# 23005_1.net
KiCad netlist of a schematic drawn in Altium Designer
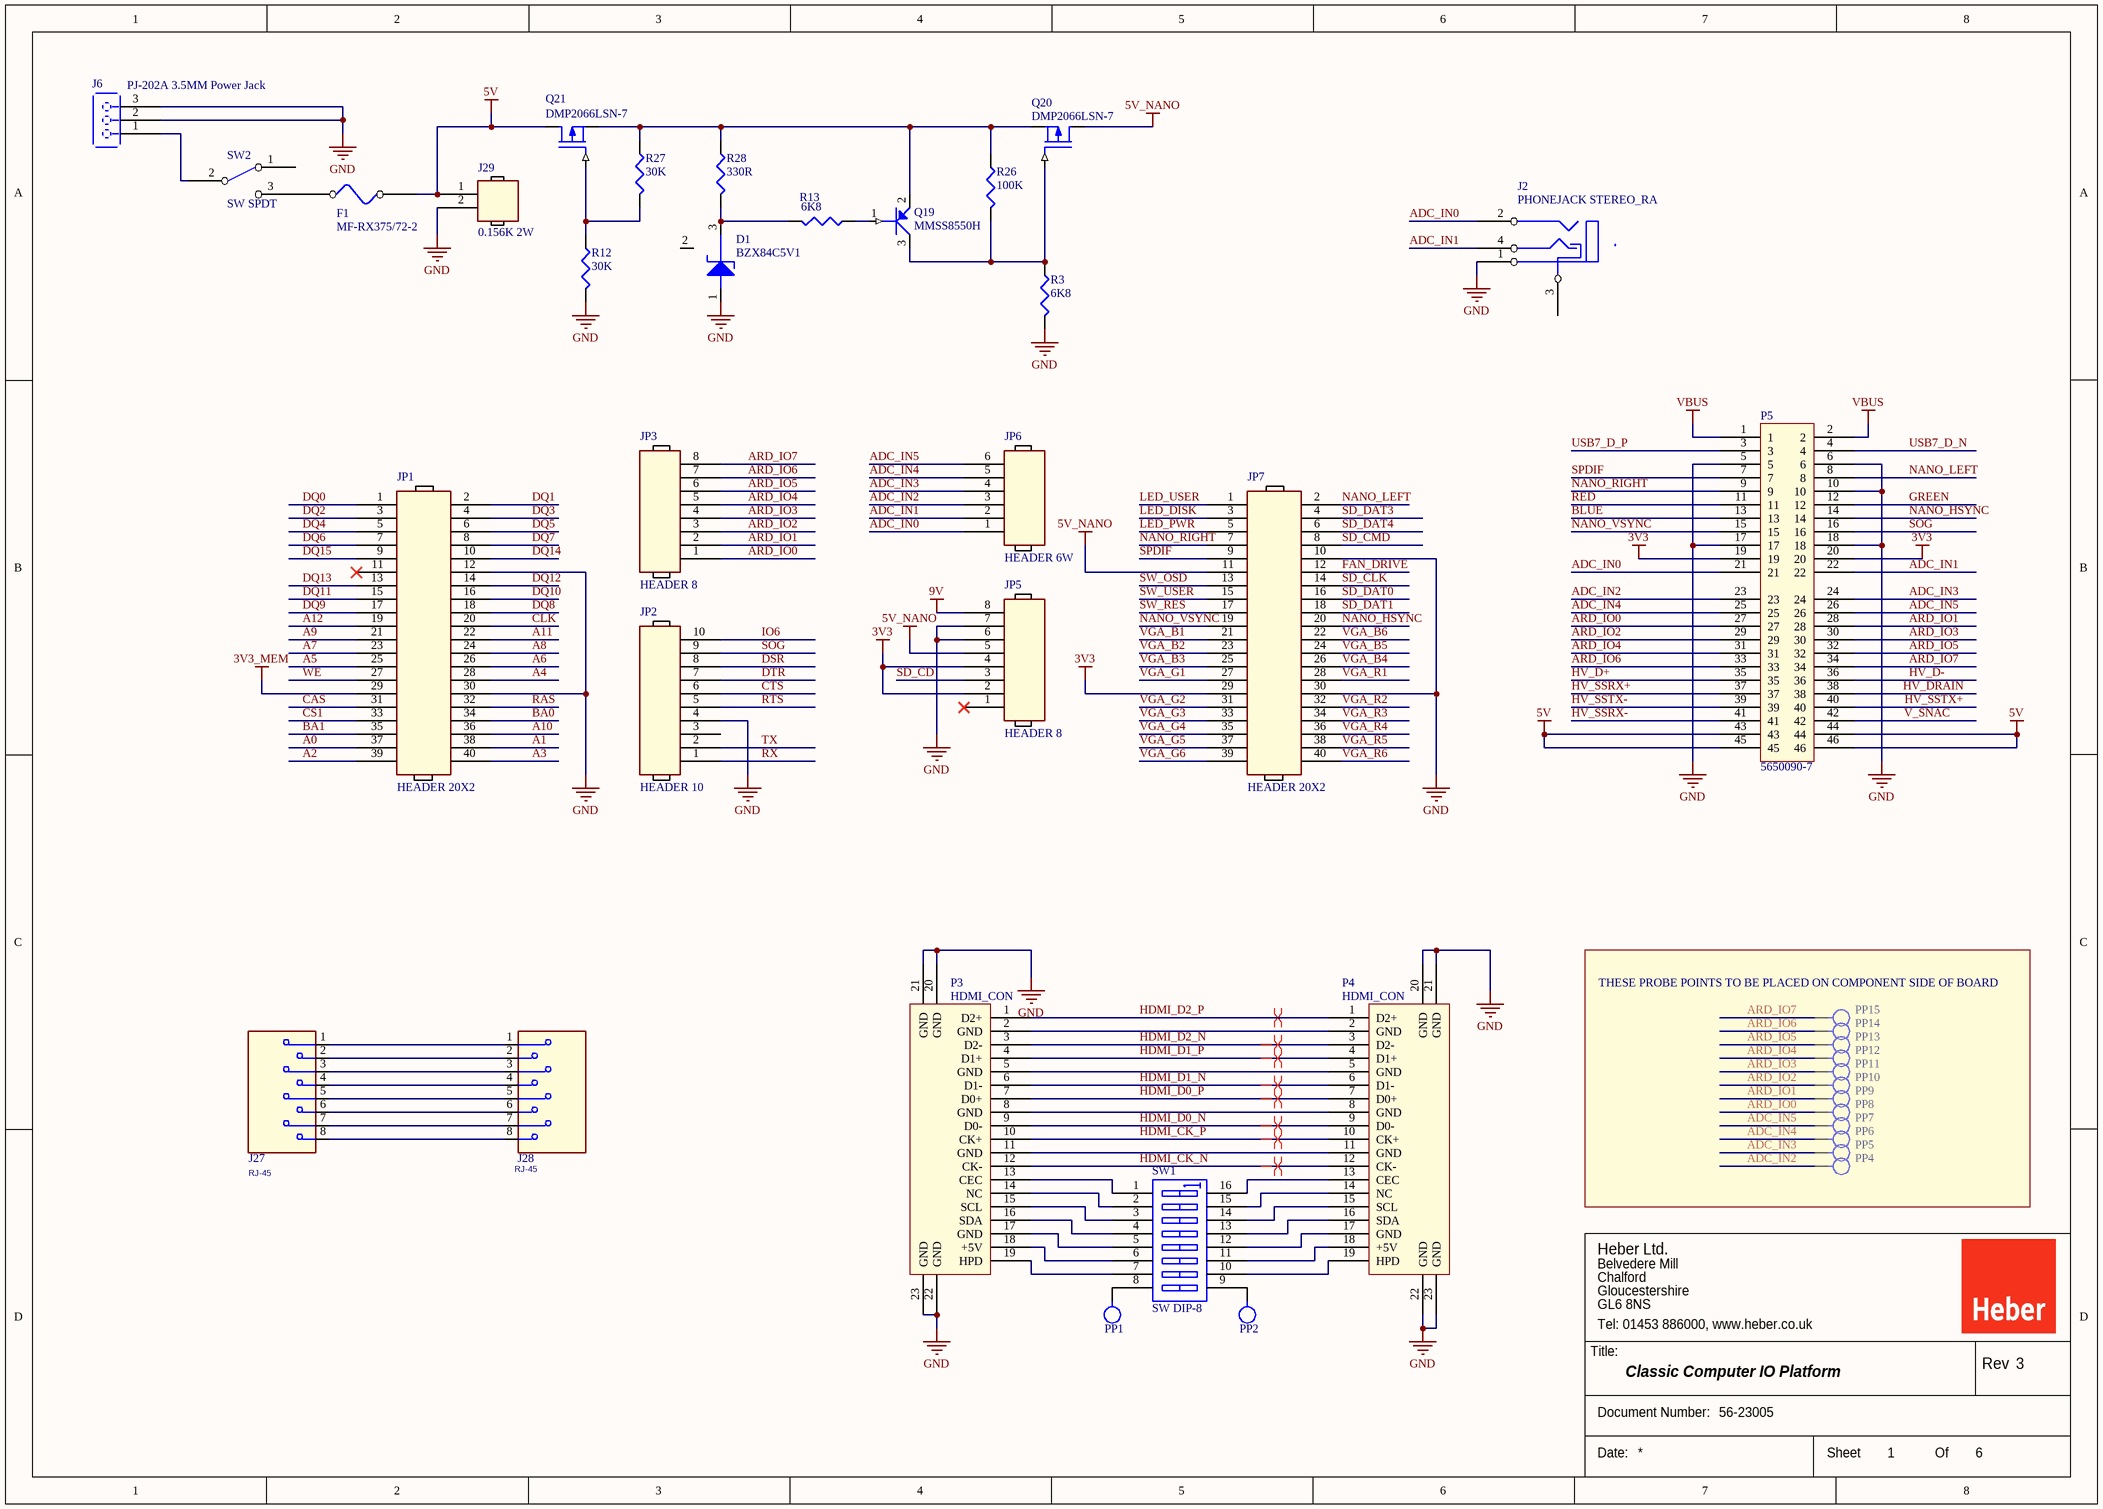
[diagram p0: 23005_1.SchDoc]

(export (version "E")
  (design (tool "Eeschema 10.0.6"))
  (components
    (comp (ref "D1")
      (value "BZX84C5V1")
      (footprint "SOT23")
      (libsource (lib "LIBRARY1_Library") (part "ZENNER_SOT23"))
    )
    (comp (ref "F1")
      (value "MF-RX375/72-2")
      (footprint "FUSE-MF-RX375/72-2")
      (libsource (lib "LIBRARY1_Library") (part "FUSE"))
    )
    (comp (ref "J2")
      (value "PHONEJACK STEREO_RA")
      (footprint "JACKSOCKET-STEREO")
      (libsource (lib "LIBRARY1_Library") (part "PHONEJACK STEREO_RA"))
    )
    (comp (ref "J6")
      (value "PJ-202A 3.5MM Power Jack")
      (footprint "CUI_PJ-202A")
      (libsource (lib "LIBRARY1_Library") (part "PLUG 3W SIL"))
    )
    (comp (ref "J27")
      (value "RJ-45")
      (footprint "P-RJHSE-XE80")
      (libsource (lib "LIBRARY1_Library") (part "RJ45"))
    )
    (comp (ref "J28") (value "RJ-45") (footprint "P-RJHSE-XE80") (libsource (lib "") (part "RJ45_1")))
    (comp (ref "J29")
      (value "0.156K 2W")
      (footprint "2W156KK")
      (libsource (lib "LIBRARY1_Library") (part "HEADER 2"))
    )
    (comp (ref "JP1")
      (value "HEADER 20X2")
      (footprint "40WHDR_20X2 - DE10-NANO")
      (libsource (lib "LIBRARY1_Library") (part "HEADER 20X2"))
    )
    (comp (ref "JP2")
      (value "HEADER 10")
      (footprint "10WSIL")
      (libsource (lib "LIBRARY1_Library") (part "HEADER 10"))
    )
    (comp (ref "JP3") (value "HEADER 8") (footprint "8WSIL") (libsource (lib "") (part "HEADER 8_1")))
    (comp (ref "JP5")
      (value "HEADER 8")
      (footprint "8WSIL")
      (libsource (lib "LIBRARY1_Library") (part "HEADER 8"))
    )
    (comp (ref "JP6")
      (value "HEADER 6W")
      (footprint "6WSIL")
      (libsource (lib "LIBRARY1_Library") (part "HEADER 6W"))
    )
    (comp (ref "JP7")
      (value "HEADER 20X2")
      (footprint "40WHDR_20X2 - DE10-NANO")
      (libsource (lib "LIBRARY1_Library") (part "HEADER 20X2"))
    )
    (comp (ref "P3") (value "HDMI_CON") (footprint "AMPFCI_1029449") (libsource (lib "") (part "HDMI_CON_1")))
    (comp (ref "P4")
      (value "HDMI_CON")
      (footprint "AMPFCI_1029449")
      (libsource (lib "LIBRARY1_Library") (part "HDMI_CON"))
    )
    (comp (ref "P5")
      (value "5650090-7")
      (footprint "AMC_RISER2")
      (libsource (lib "LIBRARY1_Library") (part "5650090-7"))
    )
    (comp (ref "PP1")
      (value "PROBEPOINT_SHORT")
      (footprint "1MM_WIRING")
      (libsource (lib "LIBRARY1_Library") (part "PROBEPOINT_SHORT"))
    )
    (comp (ref "PP2")
      (value "PROBEPOINT_SHORT")
      (footprint "1MM_WIRING")
      (libsource (lib "LIBRARY1_Library") (part "PROBEPOINT_SHORT"))
    )
    (comp (ref "PP4")
      (value "PROBEPOINT_SHORT")
      (footprint "PROBEPOINT")
      (libsource (lib "LIBRARY1_Library") (part "PROBEPOINT_SHORT"))
    )
    (comp (ref "PP5")
      (value "PROBEPOINT_SHORT")
      (footprint "PROBEPOINT")
      (libsource (lib "LIBRARY1_Library") (part "PROBEPOINT_SHORT"))
    )
    (comp (ref "PP6")
      (value "PROBEPOINT_SHORT")
      (footprint "PROBEPOINT")
      (libsource (lib "LIBRARY1_Library") (part "PROBEPOINT_SHORT"))
    )
    (comp (ref "PP7")
      (value "PROBEPOINT_SHORT")
      (footprint "PROBEPOINT")
      (libsource (lib "LIBRARY1_Library") (part "PROBEPOINT_SHORT"))
    )
    (comp (ref "PP8")
      (value "PROBEPOINT_SHORT")
      (footprint "PROBEPOINT")
      (libsource (lib "LIBRARY1_Library") (part "PROBEPOINT_SHORT"))
    )
    (comp (ref "PP9")
      (value "PROBEPOINT_SHORT")
      (footprint "PROBEPOINT")
      (libsource (lib "LIBRARY1_Library") (part "PROBEPOINT_SHORT"))
    )
    (comp (ref "PP10")
      (value "PROBEPOINT_SHORT")
      (footprint "PROBEPOINT")
      (libsource (lib "LIBRARY1_Library") (part "PROBEPOINT_SHORT"))
    )
    (comp (ref "PP11")
      (value "PROBEPOINT_SHORT")
      (footprint "PROBEPOINT")
      (libsource (lib "LIBRARY1_Library") (part "PROBEPOINT_SHORT"))
    )
    (comp (ref "PP12")
      (value "PROBEPOINT_SHORT")
      (footprint "PROBEPOINT")
      (libsource (lib "LIBRARY1_Library") (part "PROBEPOINT_SHORT"))
    )
    (comp (ref "PP13")
      (value "PROBEPOINT_SHORT")
      (footprint "PROBEPOINT")
      (libsource (lib "LIBRARY1_Library") (part "PROBEPOINT_SHORT"))
    )
    (comp (ref "PP14")
      (value "PROBEPOINT_SHORT")
      (footprint "PROBEPOINT")
      (libsource (lib "LIBRARY1_Library") (part "PROBEPOINT_SHORT"))
    )
    (comp (ref "PP15")
      (value "PROBEPOINT_SHORT")
      (footprint "PROBEPOINT")
      (libsource (lib "LIBRARY1_Library") (part "PROBEPOINT_SHORT"))
    )
    (comp (ref "Q19")
      (value "MMSS8550H")
      (footprint "SOT23")
      (libsource (lib "LIBRARY1_Library") (part "BC856AL"))
    )
    (comp (ref "Q20")
      (value "DMP2066LSN-7")
      (footprint "SOT23")
      (libsource (lib "LIBRARY1_Library") (part "MOSFET P"))
    )
    (comp (ref "Q21")
      (value "DMP2066LSN-7")
      (footprint "SOT23")
      (libsource (lib "LIBRARY1_Library") (part "MOSFET P"))
    )
    (comp (ref "R3") (value "6K8") (footprint "SM0603") (libsource (lib "LIBRARY1_Library") (part "RES")))
    (comp (ref "R12") (value "30K") (footprint "SM0603") (libsource (lib "LIBRARY1_Library") (part "RES")))
    (comp (ref "R13") (value "6K8") (footprint "SM0603") (libsource (lib "LIBRARY1_Library") (part "RES")))
    (comp (ref "R26") (value "100K") (footprint "SM0603") (libsource (lib "LIBRARY1_Library") (part "RES")))
    (comp (ref "R27") (value "30K") (footprint "SM0603") (libsource (lib "LIBRARY1_Library") (part "RES")))
    (comp (ref "R28") (value "330R") (footprint "SM0603") (libsource (lib "LIBRARY1_Library") (part "RES")))
    (comp (ref "SW1")
      (value "SW DIP-8")
      (footprint "8WSWITCH")
      (libsource (lib "LIBRARY1_Library") (part "SW DIP-8"))
    )
    (comp (ref "SW2")
      (value "SW SPDT")
      (footprint "SW_CK_L102011ml04Q")
      (libsource (lib "LIBRARY1_Library") (part "SW SPDT"))
    )
  )
  (nets
    (net (code "1") (name "/A0") (class "Default")
      (node (ref "JP1") (pin "37") (pinfunction "37_37") (pintype "passive"))
    )
    (net (code "2") (name "/A1") (class "Default")
      (node (ref "JP1") (pin "38") (pinfunction "38_38") (pintype "passive"))
    )
    (net (code "3") (name "/A2") (class "Default")
      (node (ref "JP1") (pin "39") (pinfunction "39_39") (pintype "passive"))
    )
    (net (code "4") (name "/A3") (class "Default")
      (node (ref "JP1") (pin "40") (pinfunction "40_40") (pintype "passive"))
    )
    (net (code "5") (name "/A4") (class "Default")
      (node (ref "JP1") (pin "28") (pinfunction "28_28") (pintype "passive"))
    )
    (net (code "6") (name "/A5") (class "Default")
      (node (ref "JP1") (pin "25") (pinfunction "25_25") (pintype "passive"))
    )
    (net (code "7") (name "/A6") (class "Default")
      (node (ref "JP1") (pin "26") (pinfunction "26_26") (pintype "passive"))
    )
    (net (code "8") (name "/A7") (class "Default")
      (node (ref "JP1") (pin "23") (pinfunction "23_23") (pintype "passive"))
    )
    (net (code "9") (name "/A8") (class "Default")
      (node (ref "JP1") (pin "24") (pinfunction "24_24") (pintype "passive"))
    )
    (net (code "10") (name "/A9") (class "Default")
      (node (ref "JP1") (pin "21") (pinfunction "21_21") (pintype "passive"))
    )
    (net (code "11") (name "/A10") (class "Default")
      (node (ref "JP1") (pin "36") (pinfunction "36_36") (pintype "passive"))
    )
    (net (code "12") (name "/A11") (class "Default")
      (node (ref "JP1") (pin "22") (pinfunction "22_22") (pintype "passive"))
    )
    (net (code "13") (name "/A12") (class "Default")
      (node (ref "JP1") (pin "19") (pinfunction "19_19") (pintype "passive"))
    )
    (net (code "14") (name "/ADC_IN0") (class "Default")
      (node (ref "J2") (pin "2") (pinfunction "2_2") (pintype "passive"))
      (node (ref "JP6") (pin "1") (pinfunction "1_1") (pintype "passive"))
      (node (ref "P5") (pin "21") (pinfunction "21_21") (pintype "passive"))
    )
    (net (code "15") (name "/ADC_IN1") (class "Default")
      (node (ref "J2") (pin "4") (pinfunction "4_4") (pintype "passive"))
      (node (ref "JP6") (pin "2") (pinfunction "2_2") (pintype "passive"))
      (node (ref "P5") (pin "22") (pinfunction "22_22") (pintype "passive"))
    )
    (net (code "16") (name "/ADC_IN2") (class "Default")
      (node (ref "JP6") (pin "3") (pinfunction "3_3") (pintype "passive"))
      (node (ref "P5") (pin "23") (pinfunction "23_23") (pintype "passive"))
      (node (ref "PP4") (pin "1") (pinfunction "1_1") (pintype "passive"))
    )
    (net (code "17") (name "/ADC_IN3") (class "Default")
      (node (ref "JP6") (pin "4") (pinfunction "4_4") (pintype "passive"))
      (node (ref "P5") (pin "24") (pinfunction "24_24") (pintype "passive"))
      (node (ref "PP5") (pin "1") (pinfunction "1_1") (pintype "passive"))
    )
    (net (code "18") (name "/ADC_IN4") (class "Default")
      (node (ref "JP6") (pin "5") (pinfunction "5_5") (pintype "passive"))
      (node (ref "P5") (pin "25") (pinfunction "25_25") (pintype "passive"))
      (node (ref "PP6") (pin "1") (pinfunction "1_1") (pintype "passive"))
    )
    (net (code "19") (name "/ADC_IN5") (class "Default")
      (node (ref "JP6") (pin "6") (pinfunction "6_6") (pintype "passive"))
      (node (ref "P5") (pin "26") (pinfunction "26_26") (pintype "passive"))
      (node (ref "PP7") (pin "1") (pinfunction "1_1") (pintype "passive"))
    )
    (net (code "20") (name "/ARD_IO0") (class "Default")
      (node (ref "JP3") (pin "1") (pinfunction "1_1") (pintype "passive"))
      (node (ref "P5") (pin "27") (pinfunction "27_27") (pintype "passive"))
      (node (ref "PP8") (pin "1") (pinfunction "1_1") (pintype "passive"))
    )
    (net (code "21") (name "/ARD_IO1") (class "Default")
      (node (ref "JP3") (pin "2") (pinfunction "2_2") (pintype "passive"))
      (node (ref "P5") (pin "28") (pinfunction "28_28") (pintype "passive"))
      (node (ref "PP9") (pin "1") (pinfunction "1_1") (pintype "passive"))
    )
    (net (code "22") (name "/ARD_IO2") (class "Default")
      (node (ref "JP3") (pin "3") (pinfunction "3_3") (pintype "passive"))
      (node (ref "P5") (pin "29") (pinfunction "29_29") (pintype "passive"))
      (node (ref "PP10") (pin "1") (pinfunction "1_1") (pintype "passive"))
    )
    (net (code "23") (name "/ARD_IO3") (class "Default")
      (node (ref "JP3") (pin "4") (pinfunction "4_4") (pintype "passive"))
      (node (ref "P5") (pin "30") (pinfunction "30_30") (pintype "passive"))
      (node (ref "PP11") (pin "1") (pinfunction "1_1") (pintype "passive"))
    )
    (net (code "24") (name "/ARD_IO4") (class "Default")
      (node (ref "JP3") (pin "5") (pinfunction "5_5") (pintype "passive"))
      (node (ref "P5") (pin "31") (pinfunction "31_31") (pintype "passive"))
      (node (ref "PP12") (pin "1") (pinfunction "1_1") (pintype "passive"))
    )
    (net (code "25") (name "/ARD_IO5") (class "Default")
      (node (ref "JP3") (pin "6") (pinfunction "6_6") (pintype "passive"))
      (node (ref "P5") (pin "32") (pinfunction "32_32") (pintype "passive"))
      (node (ref "PP13") (pin "1") (pinfunction "1_1") (pintype "passive"))
    )
    (net (code "26") (name "/ARD_IO6") (class "Default")
      (node (ref "JP3") (pin "7") (pinfunction "7_7") (pintype "passive"))
      (node (ref "P5") (pin "33") (pinfunction "33_33") (pintype "passive"))
      (node (ref "PP14") (pin "1") (pinfunction "1_1") (pintype "passive"))
    )
    (net (code "27") (name "/ARD_IO7") (class "Default")
      (node (ref "JP3") (pin "8") (pinfunction "8_8") (pintype "passive"))
      (node (ref "P5") (pin "34") (pinfunction "34_34") (pintype "passive"))
      (node (ref "PP15") (pin "1") (pinfunction "1_1") (pintype "passive"))
    )
    (net (code "28") (name "/BA0") (class "Default")
      (node (ref "JP1") (pin "34") (pinfunction "34_34") (pintype "passive"))
    )
    (net (code "29") (name "/BA1") (class "Default")
      (node (ref "JP1") (pin "35") (pinfunction "35_35") (pintype "passive"))
    )
    (net (code "30") (name "/BLUE") (class "Default")
      (node (ref "P5") (pin "13") (pinfunction "13_13") (pintype "passive"))
    )
    (net (code "31") (name "/CAS") (class "Default")
      (node (ref "JP1") (pin "31") (pinfunction "31_31") (pintype "passive"))
    )
    (net (code "32") (name "/CLK") (class "Default")
      (node (ref "JP1") (pin "20") (pinfunction "20_20") (pintype "passive"))
    )
    (net (code "33") (name "/CS1") (class "Default")
      (node (ref "JP1") (pin "33") (pinfunction "33_33") (pintype "passive"))
    )
    (net (code "34") (name "/CTS") (class "Default")
      (node (ref "JP2") (pin "6") (pinfunction "6_6") (pintype "passive"))
    )
    (net (code "35") (name "/DQ0") (class "Default")
      (node (ref "JP1") (pin "1") (pinfunction "1_1") (pintype "passive"))
    )
    (net (code "36") (name "/DQ1") (class "Default")
      (node (ref "JP1") (pin "2") (pinfunction "2_2") (pintype "passive"))
    )
    (net (code "37") (name "/DQ2") (class "Default")
      (node (ref "JP1") (pin "3") (pinfunction "3_3") (pintype "passive"))
    )
    (net (code "38") (name "/DQ3") (class "Default")
      (node (ref "JP1") (pin "4") (pinfunction "4_4") (pintype "passive"))
    )
    (net (code "39") (name "/DQ4") (class "Default")
      (node (ref "JP1") (pin "5") (pinfunction "5_5") (pintype "passive"))
    )
    (net (code "40") (name "/DQ5") (class "Default")
      (node (ref "JP1") (pin "6") (pinfunction "6_6") (pintype "passive"))
    )
    (net (code "41") (name "/DQ6") (class "Default")
      (node (ref "JP1") (pin "7") (pinfunction "7_7") (pintype "passive"))
    )
    (net (code "42") (name "/DQ7") (class "Default")
      (node (ref "JP1") (pin "8") (pinfunction "8_8") (pintype "passive"))
    )
    (net (code "43") (name "/DQ8") (class "Default")
      (node (ref "JP1") (pin "18") (pinfunction "18_18") (pintype "passive"))
    )
    (net (code "44") (name "/DQ9") (class "Default")
      (node (ref "JP1") (pin "17") (pinfunction "17_17") (pintype "passive"))
    )
    (net (code "45") (name "/DQ10") (class "Default")
      (node (ref "JP1") (pin "16") (pinfunction "16_16") (pintype "passive"))
    )
    (net (code "46") (name "/DQ11") (class "Default")
      (node (ref "JP1") (pin "15") (pinfunction "15_15") (pintype "passive"))
    )
    (net (code "47") (name "/DQ12") (class "Default")
      (node (ref "JP1") (pin "14") (pinfunction "14_14") (pintype "passive"))
    )
    (net (code "48") (name "/DQ13") (class "Default")
      (node (ref "JP1") (pin "13") (pinfunction "13_13") (pintype "passive"))
    )
    (net (code "49") (name "/DQ14") (class "Default")
      (node (ref "JP1") (pin "10") (pinfunction "10_10") (pintype "passive"))
    )
    (net (code "50") (name "/DQ15") (class "Default")
      (node (ref "JP1") (pin "9") (pinfunction "9_9") (pintype "passive"))
    )
    (net (code "51") (name "/DSR") (class "Default")
      (node (ref "JP2") (pin "8") (pinfunction "8_8") (pintype "passive"))
    )
    (net (code "52") (name "/DTR") (class "Default")
      (node (ref "JP2") (pin "7") (pinfunction "7_7") (pintype "passive"))
    )
    (net (code "53") (name "/FAN_DRIVE") (class "Default")
      (node (ref "JP7") (pin "12") (pinfunction "12_12") (pintype "passive"))
    )
    (net (code "54") (name "/GREEN") (class "Default")
      (node (ref "P5") (pin "12") (pinfunction "12_12") (pintype "passive"))
    )
    (net (code "55") (name "/HDMI_CK_N") (class "Default")
      (node (ref "P3") (pin "12") (pinfunction "CK-_12") (pintype "passive"))
      (node (ref "P4") (pin "12") (pinfunction "CK-_12") (pintype "passive"))
    )
    (net (code "56") (name "/HDMI_CK_P") (class "Default")
      (node (ref "P3") (pin "10") (pinfunction "CK+_10") (pintype "passive"))
      (node (ref "P4") (pin "10") (pinfunction "CK+_10") (pintype "passive"))
    )
    (net (code "57") (name "/HDMI_D0_N") (class "Default")
      (node (ref "P3") (pin "9") (pinfunction "D0-_9") (pintype "passive"))
      (node (ref "P4") (pin "9") (pinfunction "D0-_9") (pintype "passive"))
    )
    (net (code "58") (name "/HDMI_D0_P") (class "Default")
      (node (ref "P3") (pin "7") (pinfunction "D0+_7") (pintype "passive"))
      (node (ref "P4") (pin "7") (pinfunction "D0+_7") (pintype "passive"))
    )
    (net (code "59") (name "/HDMI_D1_N") (class "Default")
      (node (ref "P3") (pin "6") (pinfunction "D1-_6") (pintype "passive"))
      (node (ref "P4") (pin "6") (pinfunction "D1-_6") (pintype "passive"))
    )
    (net (code "60") (name "/HDMI_D1_P") (class "Default")
      (node (ref "P3") (pin "4") (pinfunction "D1+_4") (pintype "passive"))
      (node (ref "P4") (pin "4") (pinfunction "D1+_4") (pintype "passive"))
    )
    (net (code "61") (name "/HDMI_D2_N") (class "Default")
      (node (ref "P3") (pin "3") (pinfunction "D2-_3") (pintype "passive"))
      (node (ref "P4") (pin "3") (pinfunction "D2-_3") (pintype "passive"))
    )
    (net (code "62") (name "/HDMI_D2_P") (class "Default")
      (node (ref "P3") (pin "1") (pinfunction "D2+_1") (pintype "passive"))
      (node (ref "P4") (pin "1") (pinfunction "D2+_1") (pintype "passive"))
    )
    (net (code "63") (name "/HV_D+") (class "Default")
      (node (ref "P5") (pin "35") (pinfunction "35_35") (pintype "passive"))
    )
    (net (code "64") (name "/HV_D-") (class "Default")
      (node (ref "P5") (pin "36") (pinfunction "36_36") (pintype "passive"))
    )
    (net (code "65") (name "/HV_DRAIN") (class "Default")
      (node (ref "P5") (pin "38") (pinfunction "38_38") (pintype "passive"))
    )
    (net (code "66") (name "/HV_SSRX+") (class "Default")
      (node (ref "P5") (pin "37") (pinfunction "37_37") (pintype "passive"))
    )
    (net (code "67") (name "/HV_SSRX-") (class "Default")
      (node (ref "P5") (pin "41") (pinfunction "41_41") (pintype "passive"))
    )
    (net (code "68") (name "/HV_SSTX+") (class "Default")
      (node (ref "P5") (pin "40") (pinfunction "40_40") (pintype "passive"))
    )
    (net (code "69") (name "/HV_SSTX-") (class "Default")
      (node (ref "P5") (pin "39") (pinfunction "39_39") (pintype "passive"))
    )
    (net (code "70") (name "/IO6") (class "Default")
      (node (ref "JP2") (pin "10") (pinfunction "10_10") (pintype "passive"))
    )
    (net (code "71") (name "/LED_DISK") (class "Default")
      (node (ref "JP7") (pin "3") (pinfunction "3_3") (pintype "passive"))
    )
    (net (code "72") (name "/LED_PWR") (class "Default")
      (node (ref "JP7") (pin "5") (pinfunction "5_5") (pintype "passive"))
    )
    (net (code "73") (name "/LED_USER") (class "Default")
      (node (ref "JP7") (pin "1") (pinfunction "1_1") (pintype "passive"))
    )
    (net (code "74") (name "/NANO_HSYNC") (class "Default")
      (node (ref "JP7") (pin "20") (pinfunction "20_20") (pintype "passive"))
      (node (ref "P5") (pin "14") (pinfunction "14_14") (pintype "passive"))
    )
    (net (code "75") (name "/NANO_LEFT") (class "Default")
      (node (ref "JP7") (pin "2") (pinfunction "2_2") (pintype "passive"))
      (node (ref "P5") (pin "8") (pinfunction "8_8") (pintype "passive"))
    )
    (net (code "76") (name "/NANO_RIGHT") (class "Default")
      (node (ref "JP7") (pin "7") (pinfunction "7_7") (pintype "passive"))
      (node (ref "P5") (pin "9") (pinfunction "9_9") (pintype "passive"))
    )
    (net (code "77") (name "/NANO_VSYNC") (class "Default")
      (node (ref "JP7") (pin "19") (pinfunction "19_19") (pintype "passive"))
      (node (ref "P5") (pin "15") (pinfunction "15_15") (pintype "passive"))
    )
    (net (code "78") (name "/RAS") (class "Default")
      (node (ref "JP1") (pin "32") (pinfunction "32_32") (pintype "passive"))
    )
    (net (code "79") (name "/RED") (class "Default")
      (node (ref "P5") (pin "11") (pinfunction "11_11") (pintype "passive"))
    )
    (net (code "80") (name "/RTS") (class "Default")
      (node (ref "JP2") (pin "5") (pinfunction "5_5") (pintype "passive"))
    )
    (net (code "81") (name "/RX") (class "Default")
      (node (ref "JP2") (pin "1") (pinfunction "1_1") (pintype "passive"))
    )
    (net (code "82") (name "/SD_CD") (class "Default")
      (node (ref "JP5") (pin "3") (pinfunction "3_3") (pintype "passive"))
    )
    (net (code "83") (name "/SD_CLK") (class "Default")
      (node (ref "JP7") (pin "14") (pinfunction "14_14") (pintype "passive"))
    )
    (net (code "84") (name "/SD_CMD") (class "Default")
      (node (ref "JP7") (pin "8") (pinfunction "8_8") (pintype "passive"))
    )
    (net (code "85") (name "/SD_DAT0") (class "Default")
      (node (ref "JP7") (pin "16") (pinfunction "16_16") (pintype "passive"))
    )
    (net (code "86") (name "/SD_DAT1") (class "Default")
      (node (ref "JP7") (pin "18") (pinfunction "18_18") (pintype "passive"))
    )
    (net (code "87") (name "/SD_DAT3") (class "Default")
      (node (ref "JP7") (pin "4") (pinfunction "4_4") (pintype "passive"))
    )
    (net (code "88") (name "/SD_DAT4") (class "Default")
      (node (ref "JP7") (pin "6") (pinfunction "6_6") (pintype "passive"))
    )
    (net (code "89") (name "/SOG") (class "Default")
      (node (ref "JP2") (pin "9") (pinfunction "9_9") (pintype "passive"))
      (node (ref "P5") (pin "16") (pinfunction "16_16") (pintype "passive"))
    )
    (net (code "90") (name "/SPDIF") (class "Default")
      (node (ref "JP7") (pin "9") (pinfunction "9_9") (pintype "passive"))
      (node (ref "P5") (pin "7") (pinfunction "7_7") (pintype "passive"))
    )
    (net (code "91") (name "/SW_OSD") (class "Default")
      (node (ref "JP7") (pin "13") (pinfunction "13_13") (pintype "passive"))
    )
    (net (code "92") (name "/SW_RES") (class "Default")
      (node (ref "JP7") (pin "17") (pinfunction "17_17") (pintype "passive"))
    )
    (net (code "93") (name "/SW_USER") (class "Default")
      (node (ref "JP7") (pin "15") (pinfunction "15_15") (pintype "passive"))
    )
    (net (code "94") (name "/TX") (class "Default")
      (node (ref "JP2") (pin "2") (pinfunction "2_2") (pintype "passive"))
    )
    (net (code "95") (name "/USB7_D_N") (class "Default")
      (node (ref "P5") (pin "4") (pinfunction "4_4") (pintype "passive"))
    )
    (net (code "96") (name "/USB7_D_P") (class "Default")
      (node (ref "P5") (pin "3") (pinfunction "3_3") (pintype "passive"))
    )
    (net (code "97") (name "/VGA_B1") (class "Default")
      (node (ref "JP7") (pin "21") (pinfunction "21_21") (pintype "passive"))
    )
    (net (code "98") (name "/VGA_B2") (class "Default")
      (node (ref "JP7") (pin "23") (pinfunction "23_23") (pintype "passive"))
    )
    (net (code "99") (name "/VGA_B3") (class "Default")
      (node (ref "JP7") (pin "25") (pinfunction "25_25") (pintype "passive"))
    )
    (net (code "100") (name "/VGA_B4") (class "Default")
      (node (ref "JP7") (pin "26") (pinfunction "26_26") (pintype "passive"))
    )
    (net (code "101") (name "/VGA_B5") (class "Default")
      (node (ref "JP7") (pin "24") (pinfunction "24_24") (pintype "passive"))
    )
    (net (code "102") (name "/VGA_B6") (class "Default")
      (node (ref "JP7") (pin "22") (pinfunction "22_22") (pintype "passive"))
    )
    (net (code "103") (name "/VGA_G1") (class "Default")
      (node (ref "JP7") (pin "27") (pinfunction "27_27") (pintype "passive"))
    )
    (net (code "104") (name "/VGA_G2") (class "Default")
      (node (ref "JP7") (pin "31") (pinfunction "31_31") (pintype "passive"))
    )
    (net (code "105") (name "/VGA_G3") (class "Default")
      (node (ref "JP7") (pin "33") (pinfunction "33_33") (pintype "passive"))
    )
    (net (code "106") (name "/VGA_G4") (class "Default")
      (node (ref "JP7") (pin "35") (pinfunction "35_35") (pintype "passive"))
    )
    (net (code "107") (name "/VGA_G5") (class "Default")
      (node (ref "JP7") (pin "37") (pinfunction "37_37") (pintype "passive"))
    )
    (net (code "108") (name "/VGA_G6") (class "Default")
      (node (ref "JP7") (pin "39") (pinfunction "39_39") (pintype "passive"))
    )
    (net (code "109") (name "/VGA_R1") (class "Default")
      (node (ref "JP7") (pin "28") (pinfunction "28_28") (pintype "passive"))
    )
    (net (code "110") (name "/VGA_R2") (class "Default")
      (node (ref "JP7") (pin "32") (pinfunction "32_32") (pintype "passive"))
    )
    (net (code "111") (name "/VGA_R3") (class "Default")
      (node (ref "JP7") (pin "34") (pinfunction "34_34") (pintype "passive"))
    )
    (net (code "112") (name "/VGA_R4") (class "Default")
      (node (ref "JP7") (pin "36") (pinfunction "36_36") (pintype "passive"))
    )
    (net (code "113") (name "/VGA_R5") (class "Default")
      (node (ref "JP7") (pin "38") (pinfunction "38_38") (pintype "passive"))
    )
    (net (code "114") (name "/VGA_R6") (class "Default")
      (node (ref "JP7") (pin "40") (pinfunction "40_40") (pintype "passive"))
    )
    (net (code "115") (name "/V_SNAC") (class "Default")
      (node (ref "P5") (pin "42") (pinfunction "42_42") (pintype "passive"))
    )
    (net (code "116") (name "/WE") (class "Default")
      (node (ref "JP1") (pin "27") (pinfunction "27_27") (pintype "passive"))
    )
    (net (code "117") (name "3V3") (class "Default")
      (node (ref "JP5") (pin "2") (pinfunction "2_2") (pintype "passive"))
      (node (ref "JP5") (pin "4") (pinfunction "4_4") (pintype "passive"))
      (node (ref "JP7") (pin "29") (pinfunction "29_29") (pintype "passive"))
      (node (ref "P5") (pin "19") (pinfunction "19_19") (pintype "passive"))
      (node (ref "P5") (pin "20") (pinfunction "20_20") (pintype "passive"))
    )
    (net (code "118") (name "3V3_MEM") (class "Default")
      (node (ref "JP1") (pin "29") (pinfunction "29_29") (pintype "passive"))
    )
    (net (code "119") (name "5V") (class "Default")
      (node (ref "F1") (pin "2") (pinfunction "2_2") (pintype "passive"))
      (node (ref "J29") (pin "1") (pinfunction "1_1") (pintype "passive"))
      (node (ref "P5") (pin "43") (pinfunction "43_43") (pintype "passive"))
      (node (ref "P5") (pin "44") (pinfunction "44_44") (pintype "passive"))
      (node (ref "P5") (pin "45") (pinfunction "45_45") (pintype "passive"))
      (node (ref "P5") (pin "46") (pinfunction "46_46") (pintype "passive"))
      (node (ref "Q21") (pin "3") (pinfunction "DRAIN_3") (pintype "passive"))
    )
    (net (code "120") (name "5V_NANO") (class "Default")
      (node (ref "JP5") (pin "5") (pinfunction "5_5") (pintype "passive"))
      (node (ref "JP7") (pin "11") (pinfunction "11_11") (pintype "passive"))
      (node (ref "Q20") (pin "3") (pinfunction "DRAIN_3") (pintype "passive"))
    )
    (net (code "121") (name "9V") (class "Default")
      (node (ref "JP5") (pin "8") (pinfunction "8_8") (pintype "passive"))
    )
    (net (code "122") (name "GND") (class "Default")
      (node (ref "D1") (pin "1") (pinfunction "ANODE_1") (pintype "passive"))
      (node (ref "J2") (pin "1") (pinfunction "1_1") (pintype "passive"))
      (node (ref "J29") (pin "2") (pinfunction "2_2") (pintype "passive"))
      (node (ref "J6") (pin "2") (pinfunction "2_2") (pintype "passive"))
      (node (ref "J6") (pin "3") (pinfunction "3_3") (pintype "passive"))
      (node (ref "JP1") (pin "12") (pinfunction "12_12") (pintype "passive"))
      (node (ref "JP1") (pin "30") (pinfunction "30_30") (pintype "passive"))
      (node (ref "JP2") (pin "4") (pinfunction "4_4") (pintype "passive"))
      (node (ref "JP5") (pin "6") (pinfunction "6_6") (pintype "passive"))
      (node (ref "JP5") (pin "7") (pinfunction "7_7") (pintype "passive"))
      (node (ref "JP7") (pin "10") (pinfunction "10_10") (pintype "passive"))
      (node (ref "JP7") (pin "30") (pinfunction "30_30") (pintype "passive"))
      (node (ref "P3") (pin "20") (pinfunction "GND_20") (pintype "passive"))
      (node (ref "P3") (pin "21") (pinfunction "GND_21") (pintype "passive"))
      (node (ref "P3") (pin "22") (pinfunction "GND_22") (pintype "passive"))
      (node (ref "P3") (pin "23") (pinfunction "GND_23") (pintype "passive"))
      (node (ref "P4") (pin "20") (pinfunction "GND_20") (pintype "passive"))
      (node (ref "P4") (pin "21") (pinfunction "GND_21") (pintype "passive"))
      (node (ref "P4") (pin "22") (pinfunction "GND_22") (pintype "passive"))
      (node (ref "P4") (pin "23") (pinfunction "GND_23") (pintype "passive"))
      (node (ref "P5") (pin "10") (pinfunction "10_10") (pintype "passive"))
      (node (ref "P5") (pin "17") (pinfunction "17_17") (pintype "passive"))
      (node (ref "P5") (pin "18") (pinfunction "18_18") (pintype "passive"))
      (node (ref "P5") (pin "5") (pinfunction "5_5") (pintype "passive"))
      (node (ref "P5") (pin "6") (pinfunction "6_6") (pintype "passive"))
      (node (ref "R12") (pin "2") (pinfunction "2_2") (pintype "passive"))
      (node (ref "R3") (pin "2") (pinfunction "2_2") (pintype "passive"))
    )
    (net (code "123") (name "Net-(D1-CATHODE)") (class "Default")
      (node (ref "D1") (pin "3") (pinfunction "CATHODE_3") (pintype "passive"))
      (node (ref "R13") (pin "2") (pinfunction "2_2") (pintype "passive"))
      (node (ref "R28") (pin "2") (pinfunction "2_2") (pintype "passive"))
    )
    (net (code "124") (name "Net-(J27-Pad1)") (class "Default")
      (node (ref "J27") (pin "1") (pinfunction "1_1") (pintype "passive"))
      (node (ref "J28") (pin "1") (pinfunction "1_1") (pintype "passive"))
    )
    (net (code "125") (name "Net-(J27-Pad2)") (class "Default")
      (node (ref "J27") (pin "2") (pinfunction "2_2") (pintype "passive"))
      (node (ref "J28") (pin "2") (pinfunction "2_2") (pintype "passive"))
    )
    (net (code "126") (name "Net-(J27-Pad3)") (class "Default")
      (node (ref "J27") (pin "3") (pinfunction "3_3") (pintype "passive"))
      (node (ref "J28") (pin "3") (pinfunction "3_3") (pintype "passive"))
    )
    (net (code "127") (name "Net-(J27-Pad4)") (class "Default")
      (node (ref "J27") (pin "4") (pinfunction "4_4") (pintype "passive"))
      (node (ref "J28") (pin "4") (pinfunction "4_4") (pintype "passive"))
    )
    (net (code "128") (name "Net-(J27-Pad5)") (class "Default")
      (node (ref "J27") (pin "5") (pinfunction "5_5") (pintype "passive"))
      (node (ref "J28") (pin "5") (pinfunction "5_5") (pintype "passive"))
    )
    (net (code "129") (name "Net-(J27-Pad6)") (class "Default")
      (node (ref "J27") (pin "6") (pinfunction "6_6") (pintype "passive"))
      (node (ref "J28") (pin "6") (pinfunction "6_6") (pintype "passive"))
    )
    (net (code "130") (name "Net-(J27-Pad7)") (class "Default")
      (node (ref "J27") (pin "7") (pinfunction "7_7") (pintype "passive"))
      (node (ref "J28") (pin "7") (pinfunction "7_7") (pintype "passive"))
    )
    (net (code "131") (name "Net-(J27-Pad8)") (class "Default")
      (node (ref "J27") (pin "8") (pinfunction "8_8") (pintype "passive"))
      (node (ref "J28") (pin "8") (pinfunction "8_8") (pintype "passive"))
    )
    (net (code "132") (name "Net-(P3-+5V)") (class "Default")
      (node (ref "P3") (pin "18") (pinfunction "+5V_18") (pintype "passive"))
      (node (ref "SW1") (pin "6") (pinfunction "A6_6") (pintype "passive"))
    )
    (net (code "133") (name "Net-(P3-CEC)") (class "Default")
      (node (ref "P3") (pin "13") (pinfunction "CEC_13") (pintype "passive"))
      (node (ref "SW1") (pin "1") (pinfunction "A1_1") (pintype "passive"))
    )
    (net (code "134") (name "Net-(P3-GND-Pad2)") (class "Default")
      (node (ref "P3") (pin "2") (pinfunction "GND_2") (pintype "passive"))
      (node (ref "P4") (pin "2") (pinfunction "GND_2") (pintype "passive"))
    )
    (net (code "135") (name "Net-(P3-GND-Pad5)") (class "Default")
      (node (ref "P3") (pin "5") (pinfunction "GND_5") (pintype "passive"))
      (node (ref "P4") (pin "5") (pinfunction "GND_5") (pintype "passive"))
    )
    (net (code "136") (name "Net-(P3-GND-Pad8)") (class "Default")
      (node (ref "P3") (pin "8") (pinfunction "GND_8") (pintype "passive"))
      (node (ref "P4") (pin "8") (pinfunction "GND_8") (pintype "passive"))
    )
    (net (code "137") (name "Net-(P3-GND-Pad11)") (class "Default")
      (node (ref "P3") (pin "11") (pinfunction "GND_11") (pintype "passive"))
      (node (ref "P4") (pin "11") (pinfunction "GND_11") (pintype "passive"))
    )
    (net (code "138") (name "Net-(P3-HPD)") (class "Default")
      (node (ref "P3") (pin "19") (pinfunction "HPD_19") (pintype "passive"))
      (node (ref "SW1") (pin "7") (pinfunction "A7_7") (pintype "passive"))
    )
    (net (code "139") (name "Net-(P3-NC)") (class "Default")
      (node (ref "P3") (pin "14") (pinfunction "NC_14") (pintype "passive"))
      (node (ref "SW1") (pin "2") (pinfunction "A2_2") (pintype "passive"))
    )
    (net (code "140") (name "Net-(P3-SCL)") (class "Default")
      (node (ref "P3") (pin "15") (pinfunction "SCL_15") (pintype "passive"))
      (node (ref "SW1") (pin "3") (pinfunction "A3_3") (pintype "passive"))
    )
    (net (code "141") (name "Net-(P3-SDA)") (class "Default")
      (node (ref "P3") (pin "16") (pinfunction "SDA_16") (pintype "passive"))
      (node (ref "SW1") (pin "4") (pinfunction "A4_4") (pintype "passive"))
    )
    (net (code "142") (name "Net-(P4-+5V)") (class "Default")
      (node (ref "P4") (pin "18") (pinfunction "+5V_18") (pintype "passive"))
      (node (ref "SW1") (pin "11") (pinfunction "B6_11") (pintype "passive"))
    )
    (net (code "143") (name "Net-(P4-CEC)") (class "Default")
      (node (ref "P4") (pin "13") (pinfunction "CEC_13") (pintype "passive"))
      (node (ref "SW1") (pin "16") (pinfunction "B1_16") (pintype "passive"))
    )
    (net (code "144") (name "Net-(P4-HPD)") (class "Default")
      (node (ref "P4") (pin "19") (pinfunction "HPD_19") (pintype "passive"))
      (node (ref "SW1") (pin "10") (pinfunction "B7_10") (pintype "passive"))
    )
    (net (code "145") (name "Net-(P4-NC)") (class "Default")
      (node (ref "P4") (pin "14") (pinfunction "NC_14") (pintype "passive"))
      (node (ref "SW1") (pin "15") (pinfunction "B2_15") (pintype "passive"))
    )
    (net (code "146") (name "Net-(P4-SCL)") (class "Default")
      (node (ref "P4") (pin "15") (pinfunction "SCL_15") (pintype "passive"))
      (node (ref "SW1") (pin "14") (pinfunction "B3_14") (pintype "passive"))
    )
    (net (code "147") (name "Net-(P4-SDA)") (class "Default")
      (node (ref "P4") (pin "16") (pinfunction "SDA_16") (pintype "passive"))
      (node (ref "SW1") (pin "13") (pinfunction "B4_13") (pintype "passive"))
    )
    (net (code "148") (name "Net-(Q19-BASE)") (class "Default")
      (node (ref "Q19") (pin "1") (pinfunction "BASE_1") (pintype "input"))
      (node (ref "R13") (pin "1") (pinfunction "1_1") (pintype "passive"))
    )
    (net (code "149") (name "Net-(Q19-COLLECTOR)") (class "Default")
      (node (ref "Q19") (pin "3") (pinfunction "COLLECTOR_3") (pintype "passive"))
      (node (ref "Q20") (pin "1") (pinfunction "GATE_1") (pintype "input"))
      (node (ref "R26") (pin "2") (pinfunction "2_2") (pintype "passive"))
      (node (ref "R3") (pin "1") (pinfunction "1_1") (pintype "passive"))
    )
    (net (code "150") (name "Net-(Q19-EMITTER)") (class "Default")
      (node (ref "Q19") (pin "2") (pinfunction "EMITTER_2") (pintype "passive"))
      (node (ref "Q20") (pin "2") (pinfunction "SOURCE_2") (pintype "passive"))
      (node (ref "Q21") (pin "2") (pinfunction "SOURCE_2") (pintype "passive"))
      (node (ref "R26") (pin "1") (pinfunction "1_1") (pintype "passive"))
      (node (ref "R27") (pin "1") (pinfunction "1_1") (pintype "passive"))
      (node (ref "R28") (pin "1") (pinfunction "1_1") (pintype "passive"))
    )
    (net (code "151") (name "Net-(Q21-GATE)") (class "Default")
      (node (ref "Q21") (pin "1") (pinfunction "GATE_1") (pintype "input"))
      (node (ref "R12") (pin "1") (pinfunction "1_1") (pintype "passive"))
      (node (ref "R27") (pin "2") (pinfunction "2_2") (pintype "passive"))
    )
    (net (code "152") (name "Net-(SW1-A5)") (class "Default")
      (node (ref "P3") (pin "17") (pinfunction "GND_17") (pintype "passive"))
      (node (ref "SW1") (pin "5") (pinfunction "A5_5") (pintype "passive"))
    )
    (net (code "153") (name "Net-(SW1-A8)") (class "Default")
      (node (ref "PP1") (pin "1") (pinfunction "1_1") (pintype "passive"))
      (node (ref "SW1") (pin "8") (pinfunction "A8_8") (pintype "passive"))
    )
    (net (code "154") (name "Net-(SW1-B5)") (class "Default")
      (node (ref "P4") (pin "17") (pinfunction "GND_17") (pintype "passive"))
      (node (ref "SW1") (pin "12") (pinfunction "B5_12") (pintype "passive"))
    )
    (net (code "155") (name "Net-(SW1-B8)") (class "Default")
      (node (ref "PP2") (pin "1") (pinfunction "1_1") (pintype "passive"))
      (node (ref "SW1") (pin "9") (pinfunction "B8_9") (pintype "passive"))
    )
    (net (code "156") (name "Net-(SW2-COMMON)") (class "Default")
      (node (ref "J6") (pin "1") (pinfunction "1_1") (pintype "passive"))
      (node (ref "SW2") (pin "2") (pinfunction "COMMON_2") (pintype "passive"))
    )
    (net (code "157") (name "Net-(SW2-NO)") (class "Default")
      (node (ref "F1") (pin "1") (pinfunction "1_1") (pintype "passive"))
      (node (ref "SW2") (pin "3") (pinfunction "NO_3") (pintype "passive"))
    )
    (net (code "158") (name "VBUS") (class "Default")
      (node (ref "P5") (pin "1") (pinfunction "1_1") (pintype "passive"))
      (node (ref "P5") (pin "2") (pinfunction "2_2") (pintype "passive"))
    )
    (net (code "159") (name "unconnected-(D1-NC-Pad2)") (class "Default")
      (node (ref "D1") (pin "2") (pinfunction "NC_2") (pintype "passive"))
    )
    (net (code "160") (name "unconnected-(J2-Pad3)") (class "Default")
      (node (ref "J2") (pin "3") (pinfunction "3_3") (pintype "passive"))
    )
    (net (code "161") (name "unconnected-(JP1-Pad11)") (class "Default")
      (node (ref "JP1") (pin "11") (pinfunction "11_11") (pintype "passive+no_connect"))
    )
    (net (code "162") (name "unconnected-(JP2-Pad3)") (class "Default")
      (node (ref "JP2") (pin "3") (pinfunction "3_3") (pintype "passive"))
    )
    (net (code "163") (name "unconnected-(JP5-Pad1)") (class "Default")
      (node (ref "JP5") (pin "1") (pinfunction "1_1") (pintype "passive+no_connect"))
    )
    (net (code "164") (name "unconnected-(SW2-NC-Pad1)") (class "Default")
      (node (ref "SW2") (pin "1") (pinfunction "NC_1") (pintype "passive"))
    )
  )
)
